# Power2.net
KiCad netlist of a schematic drawn in Altium Designer
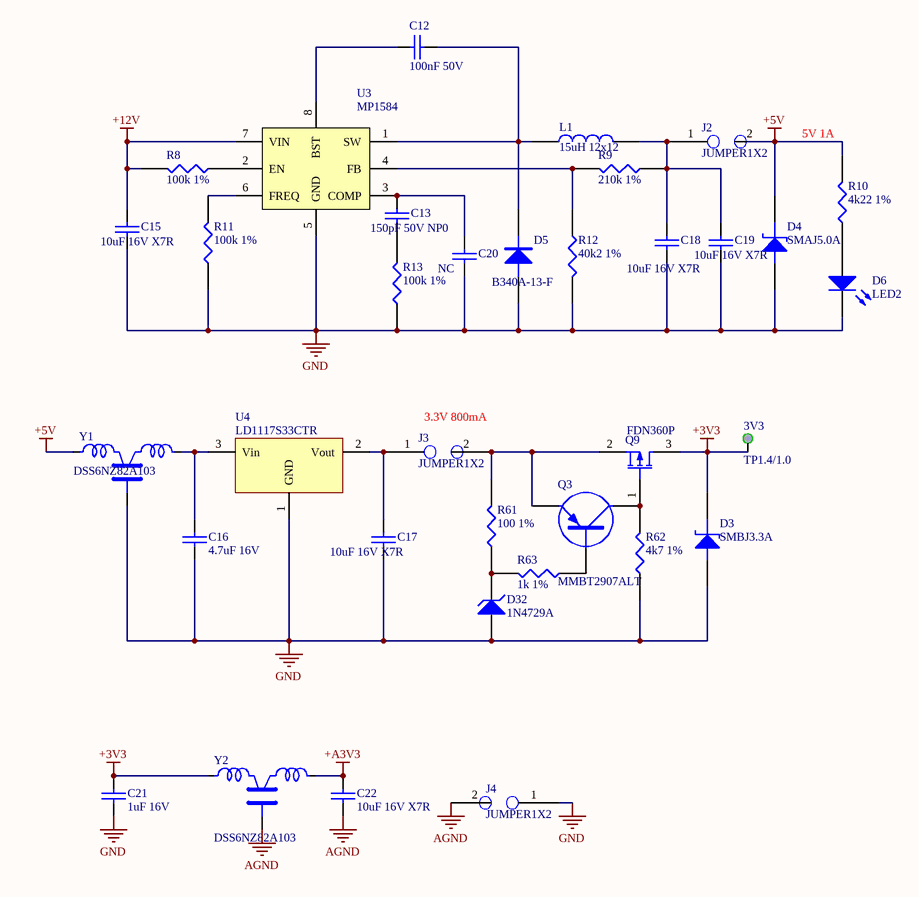
[diagram p0: Power2.SchDoc]

(export (version "E")
  (design (tool "Eeschema 10.0.6"))
  (components
    (comp (ref "3V3")
      (value "TP1.4/1.0")
      (footprint "UserPcbLib:TP1.4/1.0")
      (libsource (lib "UserSchlib") (part "TP1.4/1.0"))
    )
    (comp (ref "C12")
      (value "100nF 50V")
      (footprint "IPC-7352 Chip_Capacitor_N:CAPC2012N")
      (libsource (lib "*") (part "CAP"))
    )
    (comp (ref "C13")
      (value "150pF 50V NP0")
      (footprint "IPC-7352 Chip_Capacitor_N:CAPC2012N")
      (libsource (lib "*") (part "CAP"))
    )
    (comp (ref "C15")
      (value "10uF 16V X7R")
      (footprint "IPC-7352 Chip_Capacitor_N:CAPC3216N")
      (description "Capacitor")
      (libsource (lib "*") (part "CAP"))
    )
    (comp (ref "C16")
      (value "4.7uF 16V")
      (footprint "IPC-7352 Chip_Capacitor_N:CAPC2012N")
      (description "Capacitor")
      (libsource (lib "*") (part "CAP"))
    )
    (comp (ref "C17")
      (value "10uF 16V X7R")
      (footprint "IPC-7352 Chip_Capacitor_N:CAPC3216N")
      (libsource (lib "*") (part "CAP"))
    )
    (comp (ref "C18")
      (value "10uF 16V X7R")
      (footprint "IPC-7352 Chip_Capacitor_N:CAPC3216N")
      (libsource (lib "*") (part "CAP"))
    )
    (comp (ref "C19")
      (value "10uF 16V X7R")
      (footprint "IPC-7352 Chip_Capacitor_N:CAPC3216N")
      (libsource (lib "*") (part "CAP"))
    )
    (comp (ref "C20")
      (value "NC")
      (footprint "IPC-7352 Chip_Capacitor_N:CAPC2012N")
      (libsource (lib "*") (part "CAP"))
    )
    (comp (ref "C21")
      (value "1uF 16V")
      (footprint "IPC-7352 Chip_Capacitor_N:CAPC2012N")
      (description "Capacitor")
      (libsource (lib "") (part "CAP_1"))
    )
    (comp (ref "C22")
      (value "10uF 16V X7R")
      (footprint "IPC-7352 Chip_Capacitor_N:CAPC3216N")
      (description "Capacitor")
      (libsource (lib "*") (part "CAP"))
    )
    (comp (ref "D3")
      (value "SMBJ3.3A")
      (footprint "Small Outline Diode - 2 C-Bend Leads:DSO-C2/X2.3")
      (description "Zener Diode")
      (fields (field (name "MANUFACTURER") "Vishay"))
      (libsource (lib "*") (part "ZENER2"))
    )
    (comp (ref "D4")
      (value "SMAJ5.0A")
      (footprint "Small Outline Diode - 2 C-Bend Leads:DSO-C2/G1.6")
      (description "Zener Diode")
      (fields (field (name "MANUFACTURER") "Vishay"))
      (libsource (lib "*") (part "ZENER2"))
    )
    (comp (ref "D5")
      (value "B340A-13-F")
      (footprint "Small Outline Diode - 2 C-Bend Leads:DSO-C2/G1.6")
      (description "Zener Diode 3A 40V")
      (libsource (lib "*") (part "DIODE"))
    )
    (comp (ref "D6")
      (value "LED2")
      (footprint "3.2X1.6X1.1")
      (description "Typical RED, GREEN, YELLOW, AMBER GaAs LED")
      (fields (field (name "PUBLISHER") "Altium Limited"))
      (libsource (lib "Miscellaneous Devices") (part "LED2"))
    )
    (comp (ref "D32")
      (value "1N4729A")
      (footprint "Axial Lead Diode:DIO10.36-5.2x2.8")
      (description "Zener Diode")
      (fields (field (name "PUBLISHER") "Altium Limited"))
      (libsource (lib "Miscellaneous Devices") (part "D Zener"))
    )
    (comp (ref "J2")
      (value "JUMPER1X2")
      (footprint "UserPcbLib:JP-SOLDER-H1X2-3X2")
      (libsource (lib "*") (part "JUMPER1X2"))
    )
    (comp (ref "J3")
      (value "JUMPER1X2")
      (footprint "UserPcbLib:JP-SOLDER-H1X2-3X2")
      (libsource (lib "*") (part "JUMPER1X2"))
    )
    (comp (ref "J4")
      (value "JUMPER1X2")
      (footprint "UserPcbLib:JP-SOLDER-H1X2-3X2")
      (libsource (lib "Peter") (part "JUMPER1X2"))
    )
    (comp (ref "L1")
      (value "15uH 12x12")
      (footprint "UserPcbLib:IN-12.2X12.2MM")
      (description "Inductor 3A")
      (libsource (lib "*") (part "INDUCTOR"))
    )
    (comp (ref "Q3")
      (value "MMBT2907ALT")
      (footprint "SOT23_N:SOT23-3N")
      (description "PNP transitor")
      (libsource (lib "*") (part "MMBT3906"))
    )
    (comp (ref "Q9")
      (value "FDN360P")
      (footprint "IPC-7352 SOT23_N:SOT23-3N")
      (description "P-Channel MOSFET")
      (fields (field (name "PUBLISHER") "Altium Limited"))
      (libsource (lib "Miscellaneous Devices") (part "MOSFET-P"))
    )
    (comp (ref "R8")
      (value "100k 1%")
      (footprint "IPC-7352 Chip_Resistor_N:RESC2012N")
      (libsource (lib "*") (part "RES1"))
    )
    (comp (ref "R9")
      (value "210k 1%")
      (footprint "IPC-7352 Chip_Resistor_N:RESC2012N")
      (libsource (lib "*") (part "RES1"))
    )
    (comp (ref "R10")
      (value "4k22 1%")
      (footprint "IPC-7352 Chip_Resistor_N:RESC2012N")
      (libsource (lib "*") (part "RES1"))
    )
    (comp (ref "R11")
      (value "100k 1%")
      (footprint "IPC-7352 Chip_Resistor_N:RESC2012N")
      (libsource (lib "*") (part "RES1"))
    )
    (comp (ref "R12")
      (value "40k2 1%")
      (footprint "IPC-7352 Chip_Resistor_N:RESC2012N")
      (libsource (lib "*") (part "RES1"))
    )
    (comp (ref "R13")
      (value "100k 1%")
      (footprint "IPC-7352 Chip_Resistor_N:RESC2012N")
      (libsource (lib "*") (part "RES1"))
    )
    (comp (ref "R61")
      (value "100 1%")
      (footprint "IPC-7352 Chip_Resistor_N:RESC2012N")
      (libsource (lib "*") (part "RES1"))
    )
    (comp (ref "R62")
      (value "4k7 1%")
      (footprint "IPC-7352 Chip_Resistor_N:RESC2012N")
      (libsource (lib "*") (part "RES1"))
    )
    (comp (ref "R63")
      (value "1k 1%")
      (footprint "IPC-7352 Chip_Resistor_N:RESC2012N")
      (libsource (lib "*") (part "RES1"))
    )
    (comp (ref "U3")
      (value "MP1584")
      (footprint "UserPcbLib:SOIC8E")
      (description "3A 1.5MHz, 28V step down converter")
      (fields (field (name "MANUFACTURER") "MSP"))
      (libsource (lib "UserSchlib") (part "MP1584"))
    )
    (comp (ref "U4")
      (value "LD1117S33CTR")
      (footprint "SOT223_M:SOT223-4M")
      (description "ST Low drop voltage regulator")
      (fields (field (name "MANUFACTURER") "ST"))
      (libsource (lib "*") (part "VOLTREG"))
    )
    (comp (ref "Y1")
      (value "DSS6NZ82A103")
      (footprint "UserPcbLib:DSS6")
      (description "Murata EMI suppression filter")
      (fields (field (name "MANUFACTURER") "Murata"))
      (libsource (lib "UserSchlib") (part "DSS6"))
    )
    (comp (ref "Y2")
      (value "DSS6NZ82A103")
      (footprint "UserPcbLib:DSS6")
      (description "Murata EMI suppression filter")
      (fields (field (name "MANUFACTURER") "Murata"))
      (libsource (lib "UserSchlib") (part "DSS6"))
    )
  )
  (nets
    (net (code "1") (name "+3V3") (class "Default")
      (node (ref "3V3") (pin "1") (pinfunction "1_1") (pintype "passive"))
      (node (ref "C21") (pin "1") (pinfunction "1_1") (pintype "passive"))
      (node (ref "D3") (pin "2") (pinfunction "K_2") (pintype "passive"))
      (node (ref "Q9") (pin "3") (pinfunction "D_3") (pintype "passive"))
      (node (ref "Y2") (pin "1") (pinfunction "1_1") (pintype "passive"))
    )
    (net (code "2") (name "+5V") (class "Default")
      (node (ref "D4") (pin "2") (pinfunction "K_2") (pintype "passive"))
      (node (ref "J2") (pin "2") (pinfunction "1_2") (pintype "passive"))
      (node (ref "R10") (pin "2") (pinfunction "2_2") (pintype "passive"))
      (node (ref "Y1") (pin "1") (pinfunction "1_1") (pintype "passive"))
    )
    (net (code "3") (name "+12V") (class "Default")
      (node (ref "C15") (pin "1") (pintype "passive"))
      (node (ref "R8") (pin "2") (pinfunction "2_2") (pintype "passive"))
      (node (ref "U3") (pin "7") (pinfunction "VIN_7") (pintype "power_in"))
    )
    (net (code "4") (name "+A3V3") (class "Default")
      (node (ref "C22") (pin "1") (pintype "passive"))
      (node (ref "Y2") (pin "3") (pinfunction "3_3") (pintype "passive"))
    )
    (net (code "5") (name "AGND") (class "Default")
      (node (ref "C22") (pin "2") (pintype "passive"))
      (node (ref "J4") (pin "2") (pinfunction "1_2") (pintype "passive"))
      (node (ref "Y2") (pin "2") (pinfunction "2_2") (pintype "passive"))
    )
    (net (code "6") (name "GND") (class "Default")
      (node (ref "C15") (pin "2") (pintype "passive"))
      (node (ref "C16") (pin "2") (pintype "passive"))
      (node (ref "C17") (pin "2") (pintype "passive"))
      (node (ref "C18") (pin "2") (pintype "passive"))
      (node (ref "C19") (pin "2") (pintype "passive"))
      (node (ref "C20") (pin "2") (pintype "passive"))
      (node (ref "C21") (pin "2") (pinfunction "2_2") (pintype "passive"))
      (node (ref "D3") (pin "1") (pinfunction "A_1") (pintype "passive"))
      (node (ref "D32") (pin "1") (pinfunction "A_1") (pintype "passive"))
      (node (ref "D4") (pin "1") (pinfunction "A_1") (pintype "passive"))
      (node (ref "D5") (pin "1") (pinfunction "A_1") (pintype "passive"))
      (node (ref "D6") (pin "2") (pinfunction "K_2") (pintype "passive"))
      (node (ref "J4") (pin "1") (pinfunction "0_1") (pintype "passive"))
      (node (ref "R11") (pin "1") (pinfunction "1_1") (pintype "passive"))
      (node (ref "R12") (pin "2") (pinfunction "2_2") (pintype "passive"))
      (node (ref "R13") (pin "1") (pinfunction "1_1") (pintype "passive"))
      (node (ref "R62") (pin "1") (pinfunction "1_1") (pintype "passive"))
      (node (ref "U3") (pin "5") (pinfunction "GND_5") (pintype "power_in"))
      (node (ref "U4") (pin "1") (pinfunction "GND_1") (pintype "passive"))
      (node (ref "Y1") (pin "2") (pinfunction "2_2") (pintype "passive"))
    )
    (net (code "7") (name "Net-(C13-Pad2)") (class "Default")
      (node (ref "C13") (pin "2") (pintype "passive"))
      (node (ref "R13") (pin "2") (pinfunction "2_2") (pintype "passive"))
    )
    (net (code "8") (name "Net-(D5-K)") (class "Default")
      (node (ref "C12") (pin "2") (pintype "passive"))
      (node (ref "D5") (pin "2") (pinfunction "K_2") (pintype "passive"))
      (node (ref "L1") (pin "1") (pinfunction "1_1") (pintype "passive"))
      (node (ref "U3") (pin "1") (pinfunction "SW_1") (pintype "power_in"))
    )
    (net (code "9") (name "Net-(D6-A)") (class "Default")
      (node (ref "D6") (pin "1") (pinfunction "A_1") (pintype "passive"))
      (node (ref "R10") (pin "1") (pinfunction "1_1") (pintype "passive"))
    )
    (net (code "10") (name "Net-(D32-K)") (class "Default")
      (node (ref "D32") (pin "2") (pinfunction "K_2") (pintype "passive"))
      (node (ref "R61") (pin "1") (pinfunction "1_1") (pintype "passive"))
      (node (ref "R63") (pin "2") (pinfunction "2_2") (pintype "passive"))
    )
    (net (code "11") (name "Net-(J2-0)") (class "Default")
      (node (ref "C18") (pin "1") (pintype "passive"))
      (node (ref "C19") (pin "1") (pintype "passive"))
      (node (ref "J2") (pin "1") (pinfunction "0_1") (pintype "passive"))
      (node (ref "L1") (pin "2") (pinfunction "2_2") (pintype "passive"))
      (node (ref "R9") (pin "1") (pinfunction "1_1") (pintype "passive"))
    )
    (net (code "12") (name "Net-(J3-0)") (class "Default")
      (node (ref "C17") (pin "1") (pintype "passive"))
      (node (ref "J3") (pin "1") (pinfunction "0_1") (pintype "passive"))
      (node (ref "U4") (pin "2") (pinfunction "Vout_2") (pintype "passive"))
    )
    (net (code "13") (name "Net-(J3-1)") (class "Default")
      (node (ref "J3") (pin "2") (pinfunction "1_2") (pintype "passive"))
      (node (ref "Q3") (pin "2") (pinfunction "E_2") (pintype "passive"))
      (node (ref "Q9") (pin "2") (pinfunction "S_2") (pintype "passive"))
      (node (ref "R61") (pin "2") (pinfunction "2_2") (pintype "passive"))
    )
    (net (code "14") (name "Net-(Q3-B)") (class "Default")
      (node (ref "Q3") (pin "1") (pinfunction "B_1") (pintype "passive"))
      (node (ref "R63") (pin "1") (pinfunction "1_1") (pintype "passive"))
    )
    (net (code "15") (name "Net-(Q3-C)") (class "Default")
      (node (ref "Q3") (pin "3") (pinfunction "C_3") (pintype "passive"))
      (node (ref "Q9") (pin "1") (pinfunction "G_1") (pintype "passive"))
      (node (ref "R62") (pin "2") (pinfunction "2_2") (pintype "passive"))
    )
    (net (code "16") (name "Net-(U3-BST)") (class "Default")
      (node (ref "C12") (pin "1") (pintype "passive"))
      (node (ref "U3") (pin "8") (pinfunction "BST_8") (pintype "power_in"))
    )
    (net (code "17") (name "Net-(U3-COMP)") (class "Default")
      (node (ref "C13") (pin "1") (pintype "passive"))
      (node (ref "C20") (pin "1") (pintype "passive"))
      (node (ref "U3") (pin "3") (pinfunction "COMP_3") (pintype "power_in"))
    )
    (net (code "18") (name "Net-(U3-EN)") (class "Default")
      (node (ref "R8") (pin "1") (pinfunction "1_1") (pintype "passive"))
      (node (ref "U3") (pin "2") (pinfunction "EN_2") (pintype "power_in"))
    )
    (net (code "19") (name "Net-(U3-FB)") (class "Default")
      (node (ref "R12") (pin "1") (pinfunction "1_1") (pintype "passive"))
      (node (ref "R9") (pin "2") (pinfunction "2_2") (pintype "passive"))
      (node (ref "U3") (pin "4") (pinfunction "FB_4") (pintype "power_in"))
    )
    (net (code "20") (name "Net-(U3-FREQ)") (class "Default")
      (node (ref "R11") (pin "2") (pinfunction "2_2") (pintype "passive"))
      (node (ref "U3") (pin "6") (pinfunction "FREQ_6") (pintype "power_in"))
    )
    (net (code "21") (name "Net-(U4-Vin)") (class "Default")
      (node (ref "C16") (pin "1") (pintype "passive"))
      (node (ref "U4") (pin "3") (pinfunction "Vin_3") (pintype "passive"))
      (node (ref "Y1") (pin "3") (pinfunction "3_3") (pintype "passive"))
    )
  )
)
